# TouScruino-v0.net
KiCad netlist of a schematic drawn in EAGLE
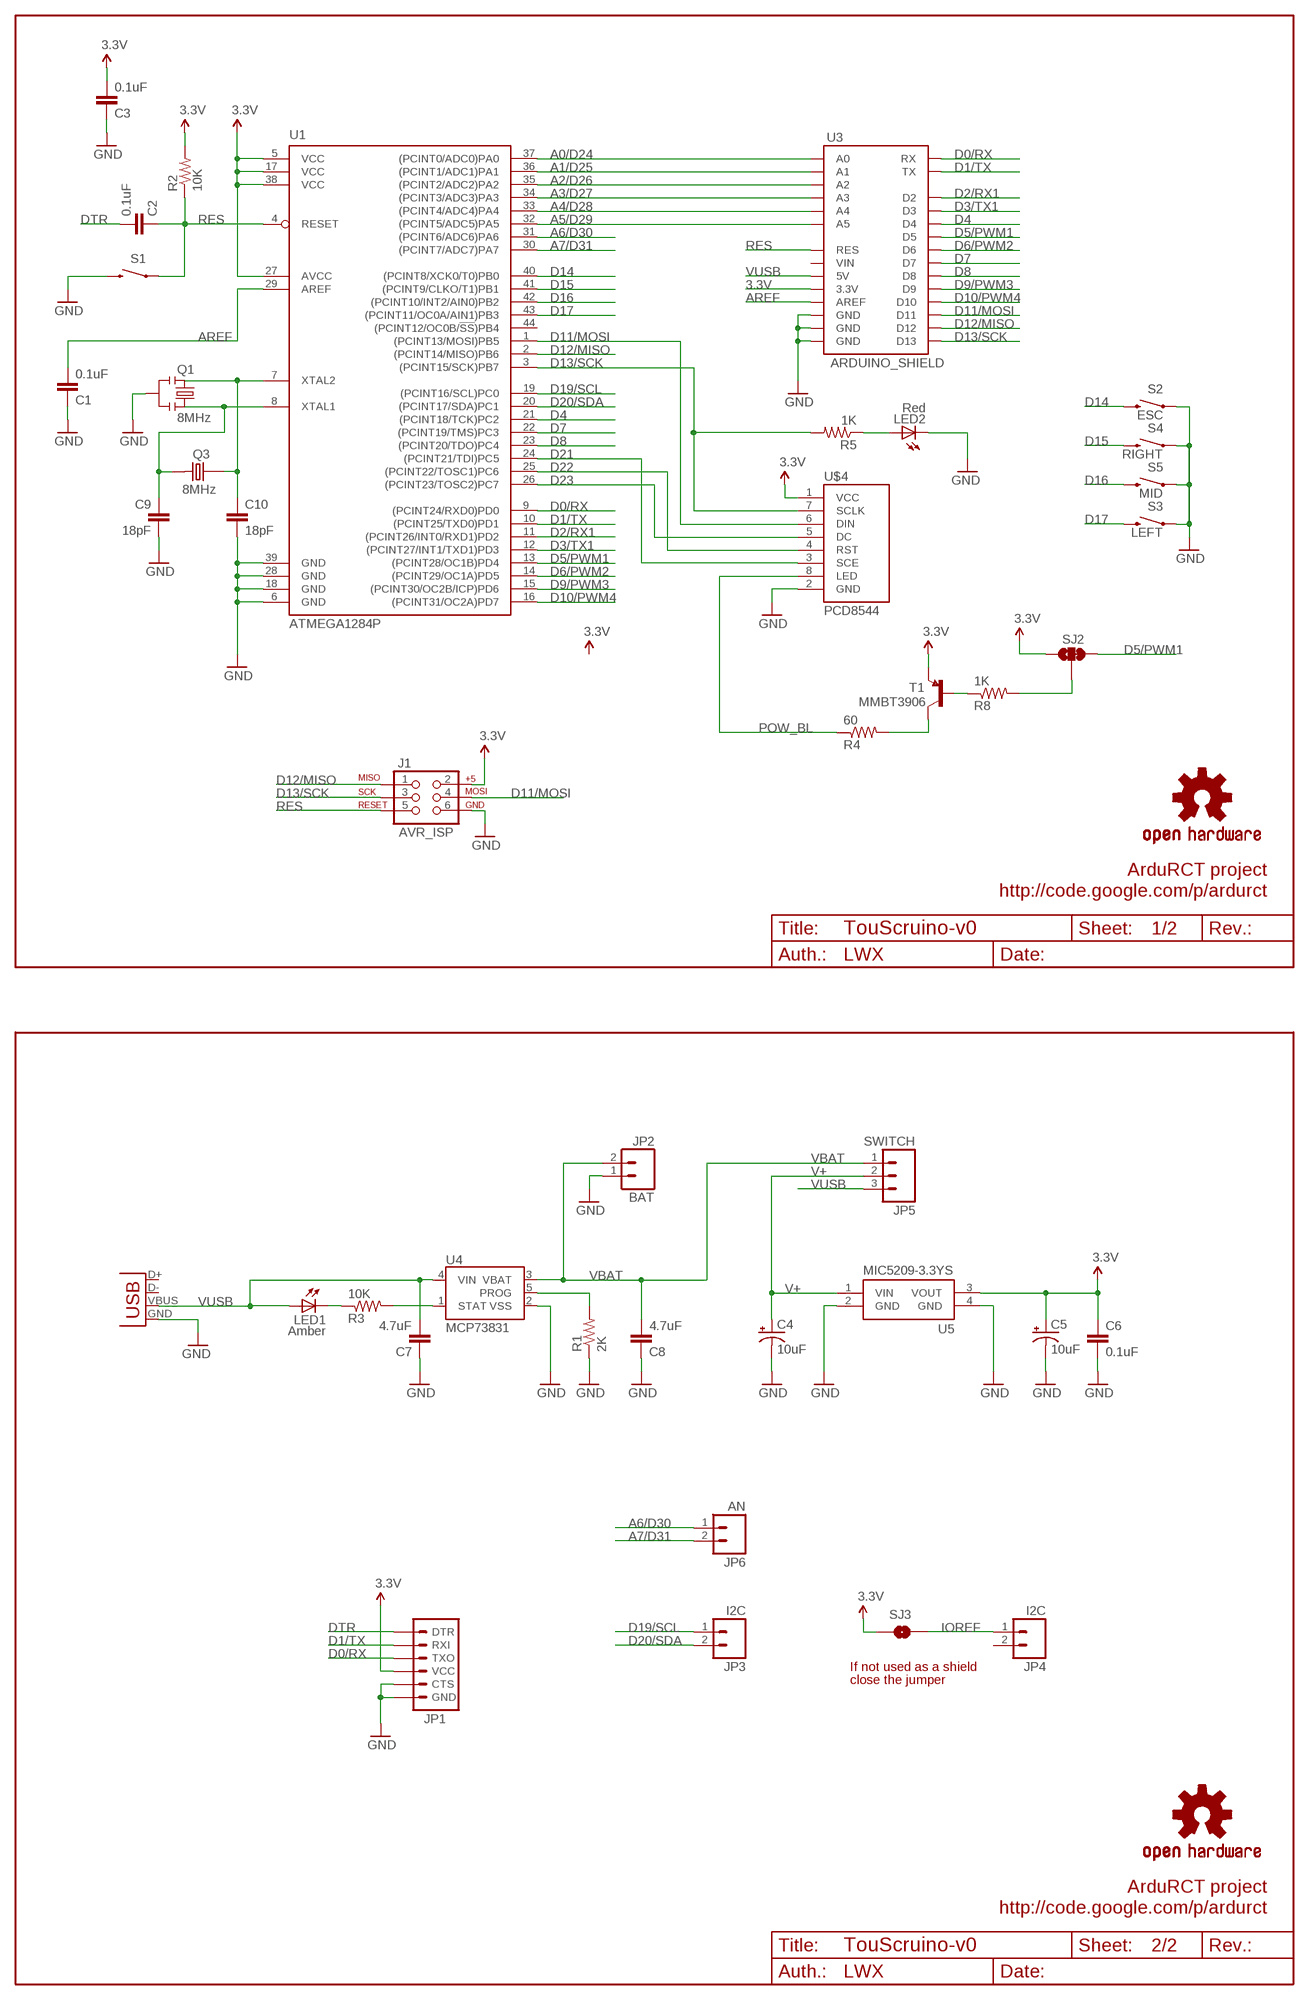
[diagram p0: schematic, sheet 1]

(export (version "E")
  (design (tool "Eeschema 10.0.6"))
  (components
    (comp (ref "C1")
      (value "0.1uF")
      (footprint "eagle-import:0805")
      (libsource (lib "eagle-import") (part "CAP0805"))
    )
    (comp (ref "C2")
      (value "0.1uF")
      (footprint "eagle-import:0805")
      (libsource (lib "eagle-import") (part "CAP0805"))
    )
    (comp (ref "C3")
      (value "0.1uF")
      (footprint "eagle-import:0805")
      (libsource (lib "eagle-import") (part "CAP0805"))
    )
    (comp (ref "C4")
      (value "10uF")
      (footprint "eagle-import:EIA3216")
      (libsource (lib "eagle-import") (part "CAP_POL1206"))
    )
    (comp (ref "C5")
      (value "10uF")
      (footprint "eagle-import:EIA3216")
      (libsource (lib "eagle-import") (part "CAP_POL1206"))
    )
    (comp (ref "C6")
      (value "0.1uF")
      (footprint "eagle-import:0805")
      (libsource (lib "eagle-import") (part "CAP0805"))
    )
    (comp (ref "C7")
      (value "4.7uF")
      (footprint "eagle-import:0805")
      (libsource (lib "eagle-import") (part "CAP0805"))
    )
    (comp (ref "C8")
      (value "4.7uF")
      (footprint "eagle-import:0805")
      (libsource (lib "eagle-import") (part "CAP0805"))
    )
    (comp (ref "C9")
      (value "18pF")
      (footprint "eagle-import:0603-CAP")
      (libsource (lib "eagle-import") (part "CAP0603-CAP"))
    )
    (comp (ref "C10")
      (value "18pF")
      (footprint "eagle-import:0603-CAP")
      (libsource (lib "eagle-import") (part "CAP0603-CAP"))
    )
    (comp (ref "J1")
      (value "AVR_ISP")
      (footprint "eagle-import:2X3")
      (libsource (lib "eagle-import") (part "AVR_SPI_PRG_6PTH"))
    )
    (comp (ref "JP1")
      (value "ARDUINO_SERIAL_PROGRAMPTH")
      (footprint "eagle-import:1X06")
      (libsource (lib "eagle-import") (part "ARDUINO_SERIAL_PROGRAMPTH"))
    )
    (comp (ref "JP2")
      (value "BAT")
      (footprint "eagle-import:JST-2-SMD")
      (libsource (lib "eagle-import") (part "M02-JST-2MM-SMT"))
    )
    (comp (ref "JP3")
      (value "I2C")
      (footprint "eagle-import:1X02")
      (libsource (lib "eagle-import") (part "M02"))
    )
    (comp (ref "JP4")
      (value "I2C")
      (footprint "eagle-import:1X02")
      (libsource (lib "eagle-import") (part "M02"))
    )
    (comp (ref "JP5")
      (value "SWITCH")
      (footprint "eagle-import:1X3_LONGPAD")
      (libsource (lib "eagle-import") (part "M03"))
    )
    (comp (ref "JP6")
      (value "AN")
      (footprint "eagle-import:1X02")
      (libsource (lib "eagle-import") (part "M02"))
    )
    (comp (ref "LED1")
      (value "Amber")
      (footprint "eagle-import:LED")
      (libsource (lib "eagle-import") (part "LED"))
    )
    (comp (ref "LED2")
      (value "Red")
      (footprint "eagle-import:LED-0805")
      (libsource (lib "eagle-import") (part "LED805"))
    )
    (comp (ref "Q1")
      (value "8MHz")
      (footprint "eagle-import:RESONATOR-SMD")
      (libsource (lib "eagle-import") (part "RESONATORSMD"))
    )
    (comp (ref "Q3")
      (value "8MHz")
      (footprint "eagle-import:CRYSTAL_5X3.2")
      (libsource (lib "eagle-import") (part "CRYSTAL_5X3.2"))
    )
    (comp (ref "R1")
      (value "2K")
      (footprint "eagle-import:0805")
      (libsource (lib "eagle-import") (part "RESISTOR0805-RES"))
    )
    (comp (ref "R2")
      (value "10K")
      (footprint "eagle-import:0805")
      (libsource (lib "eagle-import") (part "RESISTOR0805-RES"))
    )
    (comp (ref "R3")
      (value "10K")
      (footprint "eagle-import:0805")
      (libsource (lib "eagle-import") (part "RESISTOR0805-RES"))
    )
    (comp (ref "R4")
      (value "60")
      (footprint "eagle-import:0805")
      (libsource (lib "eagle-import") (part "RESISTOR0805-RES"))
    )
    (comp (ref "R5")
      (value "1K")
      (footprint "eagle-import:0805")
      (libsource (lib "eagle-import") (part "RESISTOR0805-RES"))
    )
    (comp (ref "R8")
      (value "1K")
      (footprint "eagle-import:0805")
      (libsource (lib "eagle-import") (part "RESISTOR0805-RES"))
    )
    (comp (ref "S1")
      (value "SWITCH-MOMENTARY-2SMD")
      (footprint "eagle-import:TACTILE_SWITCH_SMD@1")
      (libsource (lib "eagle-import") (part "SWITCH-MOMENTARY-2SMD"))
    )
    (comp (ref "S2")
      (value "ESC")
      (footprint "eagle-import:TACTILE_SWITCH_SMD")
      (libsource (lib "eagle-import") (part "SWITCH_SMD"))
    )
    (comp (ref "S3")
      (value "LEFT")
      (footprint "eagle-import:TACTILE_SWITCH_SMD")
      (libsource (lib "eagle-import") (part "SWITCH_SMD"))
    )
    (comp (ref "S4")
      (value "RIGHT")
      (footprint "eagle-import:TACTILE_SWITCH_SMD")
      (libsource (lib "eagle-import") (part "SWITCH_SMD"))
    )
    (comp (ref "S5")
      (value "MID")
      (footprint "eagle-import:TACTILE_SWITCH_SMD")
      (libsource (lib "eagle-import") (part "SWITCH_SMD"))
    )
    (comp (ref "SJ2")
      (value "SJ_2WAYS_1-2")
      (footprint "eagle-import:SJ_2WAYS_1-2_S")
      (libsource (lib "eagle-import") (part "SJ_2WAYS_1-2"))
    )
    (comp (ref "SJ3")
      (value "SOLDERJUMPERNO")
      (footprint "eagle-import:SJ_2S-NO")
      (libsource (lib "eagle-import") (part "SOLDERJUMPERNO"))
    )
    (comp (ref "T1")
      (value "MMBT3906")
      (footprint "eagle-import:SOT23-3")
      (libsource (lib "eagle-import") (part "TRANSISTOR_PNPSMD"))
    )
    (comp (ref "U$3")
      (value "OSHW-LOGOM")
      (footprint "eagle-import:OSHW-LOGO-M")
      (libsource (lib "eagle-import") (part "OSHW-LOGOM"))
    )
    (comp (ref "U$4")
      (value "PCD8544")
      (footprint "eagle-import:PCD8544")
      (libsource (lib "eagle-import") (part "PCD8544"))
    )
    (comp (ref "U$5")
      (value "OSHW-LOGOM")
      (footprint "eagle-import:OSHW-LOGO-M")
      (libsource (lib "eagle-import") (part "OSHW-LOGOM"))
    )
    (comp (ref "U1")
      (value "ATMEGA1284P")
      (footprint "eagle-import:TQFP44")
      (libsource (lib "eagle-import") (part "ATMEGA324A"))
    )
    (comp (ref "U3")
      (value "ARDUINO_SHIELD")
      (footprint "eagle-import:ARDUINO_SHIELD")
      (libsource (lib "eagle-import") (part "ARDUINO_SHIELD"))
    )
    (comp (ref "U4")
      (value "MCP73831")
      (footprint "eagle-import:SOT23-5")
      (libsource (lib "eagle-import") (part "MCP73831"))
    )
    (comp (ref "U5")
      (value "MIC5209-3.3YS")
      (footprint "eagle-import:SOT223")
      (libsource (lib "eagle-import") (part "MIC5209"))
    )
    (comp (ref "X1")
      (value "USBSMD")
      (footprint "eagle-import:USB-MINIB")
      (libsource (lib "eagle-import") (part "USBSMD"))
    )
  )
  (nets
    (net (code "1") (name "/A0{slash}D24") (class "Default")
      (node (ref "U1") (pin "37") (pinfunction "(PCINT0/ADC0)PA0_37") (pintype "bidirectional"))
      (node (ref "U3") (pin "A0") (pinfunction "A0_A0") (pintype "bidirectional"))
    )
    (net (code "2") (name "/A1{slash}D25") (class "Default")
      (node (ref "U1") (pin "36") (pinfunction "(PCINT1/ADC1)PA1_36") (pintype "bidirectional"))
      (node (ref "U3") (pin "A1") (pinfunction "A1_A1") (pintype "bidirectional"))
    )
    (net (code "3") (name "/A2{slash}D26") (class "Default")
      (node (ref "U1") (pin "35") (pinfunction "(PCINT2/ADC2)PA2_35") (pintype "bidirectional"))
      (node (ref "U3") (pin "A2") (pinfunction "A2_A2") (pintype "bidirectional"))
    )
    (net (code "4") (name "/A3{slash}D27") (class "Default")
      (node (ref "U1") (pin "34") (pinfunction "(PCINT3/ADC3)PA3_34") (pintype "bidirectional"))
      (node (ref "U3") (pin "A3") (pinfunction "A3_A3") (pintype "bidirectional"))
    )
    (net (code "5") (name "/A4{slash}D28") (class "Default")
      (node (ref "U1") (pin "33") (pinfunction "(PCINT4/ADC4)PA4_33") (pintype "bidirectional"))
      (node (ref "U3") (pin "A4") (pinfunction "A4_A4") (pintype "bidirectional"))
    )
    (net (code "6") (name "/A5{slash}D29") (class "Default")
      (node (ref "U1") (pin "32") (pinfunction "(PCINT5/ADC5)PA5_32") (pintype "bidirectional"))
      (node (ref "U3") (pin "A5") (pinfunction "A5_A5") (pintype "bidirectional"))
    )
    (net (code "7") (name "/A6{slash}D30") (class "Default")
      (node (ref "JP6") (pin "1") (pinfunction "1_1") (pintype "passive"))
      (node (ref "U1") (pin "31") (pinfunction "(PCINT6/ADC6)PA6_31") (pintype "bidirectional"))
    )
    (net (code "8") (name "/A7{slash}D31") (class "Default")
      (node (ref "JP6") (pin "2") (pinfunction "2_2") (pintype "passive"))
      (node (ref "U1") (pin "30") (pinfunction "(PCINT7/ADC7)PA7_30") (pintype "bidirectional"))
    )
    (net (code "9") (name "/AREF") (class "Default")
      (node (ref "C1") (pin "2") (pinfunction "2_2") (pintype "passive"))
      (node (ref "U1") (pin "29") (pinfunction "AREF_29") (pintype "passive"))
      (node (ref "U3") (pin "AREF") (pinfunction "AREF_AREF") (pintype "bidirectional"))
    )
    (net (code "10") (name "/D0{slash}RX") (class "Default")
      (node (ref "JP1") (pin "3") (pinfunction "TXO_3") (pintype "passive"))
      (node (ref "U1") (pin "9") (pinfunction "(PCINT24/RXD0)PD0_9") (pintype "bidirectional"))
      (node (ref "U3") (pin "RX") (pinfunction "RX_RX") (pintype "bidirectional"))
    )
    (net (code "11") (name "/D1{slash}TX") (class "Default")
      (node (ref "JP1") (pin "2") (pinfunction "RXI_2") (pintype "passive"))
      (node (ref "U1") (pin "10") (pinfunction "(PCINT25/TXD0)PD1_10") (pintype "bidirectional"))
      (node (ref "U3") (pin "TX") (pinfunction "TX_TX") (pintype "bidirectional"))
    )
    (net (code "12") (name "/D2{slash}RX1") (class "Default")
      (node (ref "U1") (pin "11") (pinfunction "(PCINT26/INT0/RXD1)PD2_11") (pintype "bidirectional"))
      (node (ref "U3") (pin "D2") (pinfunction "D2_D2") (pintype "bidirectional"))
    )
    (net (code "13") (name "/D3{slash}TX1") (class "Default")
      (node (ref "U1") (pin "12") (pinfunction "(PCINT27/INT1/TXD1)PD3_12") (pintype "bidirectional"))
      (node (ref "U3") (pin "D3") (pinfunction "D3_D3") (pintype "bidirectional"))
    )
    (net (code "14") (name "/D4") (class "Default")
      (node (ref "U1") (pin "21") (pinfunction "(PCINT18/TCK)PC2_21") (pintype "output"))
      (node (ref "U3") (pin "D4") (pinfunction "D4_D4") (pintype "bidirectional"))
    )
    (net (code "15") (name "/D5{slash}PWM1") (class "Default")
      (node (ref "SJ2") (pin "1") (pinfunction "1_1") (pintype "passive"))
      (node (ref "U1") (pin "13") (pinfunction "(PCINT28/OC1B)PD4_13") (pintype "bidirectional"))
      (node (ref "U3") (pin "D5") (pinfunction "D5_D5") (pintype "bidirectional"))
    )
    (net (code "16") (name "/D6{slash}PWM2") (class "Default")
      (node (ref "U1") (pin "14") (pinfunction "(PCINT29/OC1A)PD5_14") (pintype "bidirectional"))
      (node (ref "U3") (pin "D6") (pinfunction "D6_D6") (pintype "bidirectional"))
    )
    (net (code "17") (name "/D7") (class "Default")
      (node (ref "U1") (pin "22") (pinfunction "(PCINT19/TMS)PC3_22") (pintype "output"))
      (node (ref "U3") (pin "D7") (pinfunction "D7_D7") (pintype "bidirectional"))
    )
    (net (code "18") (name "/D8") (class "Default")
      (node (ref "U1") (pin "23") (pinfunction "(PCINT20/TDO)PC4_23") (pintype "output"))
      (node (ref "U3") (pin "D8") (pinfunction "D8_D8") (pintype "bidirectional"))
    )
    (net (code "19") (name "/D9{slash}PWM3") (class "Default")
      (node (ref "U1") (pin "15") (pinfunction "(PCINT30/OC2B/ICP)PD6_15") (pintype "bidirectional"))
      (node (ref "U3") (pin "D9") (pinfunction "D9_D9") (pintype "bidirectional"))
    )
    (net (code "20") (name "/D10{slash}PWM4") (class "Default")
      (node (ref "U1") (pin "16") (pinfunction "(PCINT31/OC2A)PD7_16") (pintype "bidirectional"))
      (node (ref "U3") (pin "D10") (pinfunction "D10_D10") (pintype "bidirectional"))
    )
    (net (code "21") (name "/D11{slash}MOSI") (class "Default")
      (node (ref "J1") (pin "4") (pinfunction "4_4") (pintype "passive"))
      (node (ref "U$4") (pin "6") (pinfunction "DIN_6") (pintype "bidirectional"))
      (node (ref "U1") (pin "1") (pinfunction "(PCINT13/MOSI)PB5_1") (pintype "bidirectional"))
      (node (ref "U3") (pin "D11") (pinfunction "D11_D11") (pintype "bidirectional"))
    )
    (net (code "22") (name "/D12{slash}MISO") (class "Default")
      (node (ref "J1") (pin "1") (pinfunction "1_1") (pintype "passive"))
      (node (ref "U1") (pin "2") (pinfunction "(PCINT14/MISO)PB6_2") (pintype "bidirectional"))
      (node (ref "U3") (pin "D12") (pinfunction "D12_D12") (pintype "bidirectional"))
    )
    (net (code "23") (name "/D13{slash}SCK") (class "Default")
      (node (ref "J1") (pin "3") (pinfunction "3_3") (pintype "passive"))
      (node (ref "R5") (pin "2") (pinfunction "2_2") (pintype "passive"))
      (node (ref "U$4") (pin "7") (pinfunction "SCLK_7") (pintype "bidirectional"))
      (node (ref "U1") (pin "3") (pinfunction "(PCINT15/SCK)PB7_3") (pintype "bidirectional"))
      (node (ref "U3") (pin "D13") (pinfunction "D13_D13") (pintype "bidirectional"))
    )
    (net (code "24") (name "/D14") (class "Default")
      (node (ref "S2") (pin "3") (pinfunction "2_3") (pintype "passive"))
      (node (ref "U1") (pin "40") (pinfunction "(PCINT8/XCK0/T0)PB0_40") (pintype "bidirectional"))
    )
    (net (code "25") (name "/D15") (class "Default")
      (node (ref "S4") (pin "3") (pinfunction "2_3") (pintype "passive"))
      (node (ref "U1") (pin "41") (pinfunction "(PCINT9/CLKO/T1)PB1_41") (pintype "bidirectional"))
    )
    (net (code "26") (name "/D16") (class "Default")
      (node (ref "S5") (pin "3") (pinfunction "2_3") (pintype "passive"))
      (node (ref "U1") (pin "42") (pinfunction "(PCINT10/INT2/AIN0)PB2_42") (pintype "bidirectional"))
    )
    (net (code "27") (name "/D17") (class "Default")
      (node (ref "S3") (pin "3") (pinfunction "2_3") (pintype "passive"))
      (node (ref "U1") (pin "43") (pinfunction "(PCINT11/OC0A/AIN1)PB3_43") (pintype "bidirectional"))
    )
    (net (code "28") (name "/D19{slash}SCL") (class "Default")
      (node (ref "JP3") (pin "1") (pinfunction "1_1") (pintype "passive"))
      (node (ref "U1") (pin "19") (pinfunction "(PCINT16/SCL)PC0_19") (pintype "output"))
    )
    (net (code "29") (name "/D20{slash}SDA") (class "Default")
      (node (ref "JP3") (pin "2") (pinfunction "2_2") (pintype "passive"))
      (node (ref "U1") (pin "20") (pinfunction "(PCINT17/SDA)PC1_20") (pintype "output"))
    )
    (net (code "30") (name "/D21") (class "Default")
      (node (ref "U$4") (pin "3") (pinfunction "SCE_3") (pintype "bidirectional"))
      (node (ref "U1") (pin "24") (pinfunction "(PCINT21/TDI)PC5_24") (pintype "output"))
    )
    (net (code "31") (name "/D22") (class "Default")
      (node (ref "U$4") (pin "4") (pinfunction "RST_4") (pintype "bidirectional"))
      (node (ref "U1") (pin "25") (pinfunction "(PCINT22/TOSC1)PC6_25") (pintype "output"))
    )
    (net (code "32") (name "/D23") (class "Default")
      (node (ref "U$4") (pin "5") (pinfunction "DC_5") (pintype "bidirectional"))
      (node (ref "U1") (pin "26") (pinfunction "(PCINT23/TOSC2)PC7_26") (pintype "output"))
    )
    (net (code "33") (name "/DTR") (class "Default")
      (node (ref "C2") (pin "2") (pinfunction "2_2") (pintype "passive"))
      (node (ref "JP1") (pin "1") (pinfunction "DTR_1") (pintype "passive"))
    )
    (net (code "34") (name "/IOREF") (class "Default")
      (node (ref "JP4") (pin "1") (pinfunction "1_1") (pintype "passive"))
      (node (ref "SJ3") (pin "2") (pinfunction "2_2") (pintype "passive"))
    )
    (net (code "35") (name "/POW_BL") (class "Default")
      (node (ref "R4") (pin "1") (pinfunction "1_1") (pintype "passive"))
      (node (ref "U$4") (pin "8") (pinfunction "LED_8") (pintype "bidirectional"))
    )
    (net (code "36") (name "/RES") (class "Default")
      (node (ref "C2") (pin "1") (pinfunction "1_1") (pintype "passive"))
      (node (ref "J1") (pin "5") (pinfunction "5_5") (pintype "passive"))
      (node (ref "R2") (pin "1") (pinfunction "1_1") (pintype "passive"))
      (node (ref "S1") (pin "1") (pinfunction "1_1") (pintype "passive"))
      (node (ref "U1") (pin "4") (pinfunction "RESET_4") (pintype "input"))
      (node (ref "U3") (pin "RES") (pinfunction "RES_RES") (pintype "bidirectional"))
    )
    (net (code "37") (name "/V+") (class "Default")
      (node (ref "C4") (pin "A") (pinfunction "+_A") (pintype "passive"))
      (node (ref "JP5") (pin "2") (pinfunction "2_2") (pintype "passive"))
      (node (ref "U5") (pin "1") (pinfunction "VIN_1") (pintype "bidirectional"))
    )
    (net (code "38") (name "/VBAT") (class "Default")
      (node (ref "C8") (pin "2") (pinfunction "2_2") (pintype "passive"))
      (node (ref "JP2") (pin "2") (pinfunction "2_2") (pintype "passive"))
      (node (ref "JP5") (pin "1") (pinfunction "1_1") (pintype "passive"))
      (node (ref "U4") (pin "3") (pinfunction "VBAT_3") (pintype "power_in"))
    )
    (net (code "39") (name "/VUSB") (class "Default")
      (node (ref "C7") (pin "2") (pinfunction "2_2") (pintype "passive"))
      (node (ref "JP5") (pin "3") (pinfunction "3_3") (pintype "passive"))
      (node (ref "LED1") (pin "A1") (pinfunction "A_A1") (pintype "passive"))
      (node (ref "U3") (pin "5V") (pinfunction "5V_5V") (pintype "bidirectional"))
      (node (ref "U4") (pin "4") (pinfunction "VIN_4") (pintype "power_in"))
      (node (ref "X1") (pin "VBUS") (pinfunction "VBUS_VBUS") (pintype "bidirectional"))
    )
    (net (code "40") (name "3.3V") (class "Default")
      (node (ref "C3") (pin "2") (pinfunction "2_2") (pintype "passive"))
      (node (ref "C5") (pin "A") (pinfunction "+_A") (pintype "passive"))
      (node (ref "C6") (pin "1") (pinfunction "1_1") (pintype "passive"))
      (node (ref "J1") (pin "2") (pinfunction "2_2") (pintype "passive"))
      (node (ref "JP1") (pin "4") (pinfunction "VCC_4") (pintype "passive"))
      (node (ref "R2") (pin "2") (pinfunction "2_2") (pintype "passive"))
      (node (ref "SJ2") (pin "3") (pinfunction "3_3") (pintype "passive"))
      (node (ref "SJ3") (pin "1") (pinfunction "1_1") (pintype "passive"))
      (node (ref "T1") (pin "2") (pinfunction "E_2") (pintype "passive"))
      (node (ref "U$4") (pin "1") (pinfunction "VCC_1") (pintype "bidirectional"))
      (node (ref "U1") (pin "17") (pinfunction "VCC_17") (pintype "power_in"))
      (node (ref "U1") (pin "27") (pinfunction "AVCC_27") (pintype "power_in"))
      (node (ref "U1") (pin "38") (pinfunction "VCC_38") (pintype "power_in"))
      (node (ref "U1") (pin "5") (pinfunction "VCC_5") (pintype "power_in"))
      (node (ref "U3") (pin "3.3V") (pinfunction "3.3V_3.3V") (pintype "bidirectional"))
      (node (ref "U5") (pin "3") (pinfunction "VOUT_3") (pintype "bidirectional"))
    )
    (net (code "41") (name "GND") (class "Default")
      (node (ref "C1") (pin "1") (pinfunction "1_1") (pintype "passive"))
      (node (ref "C10") (pin "2") (pinfunction "2_2") (pintype "passive"))
      (node (ref "C3") (pin "1") (pinfunction "1_1") (pintype "passive"))
      (node (ref "C4") (pin "C") (pinfunction "-_C") (pintype "passive"))
      (node (ref "C5") (pin "C") (pinfunction "-_C") (pintype "passive"))
      (node (ref "C6") (pin "2") (pinfunction "2_2") (pintype "passive"))
      (node (ref "C7") (pin "1") (pinfunction "1_1") (pintype "passive"))
      (node (ref "C8") (pin "1") (pinfunction "1_1") (pintype "passive"))
      (node (ref "C9") (pin "2") (pinfunction "2_2") (pintype "passive"))
      (node (ref "J1") (pin "6") (pinfunction "6_6") (pintype "passive"))
      (node (ref "JP1") (pin "5") (pinfunction "CTS_5") (pintype "passive"))
      (node (ref "JP1") (pin "6") (pinfunction "GND_6") (pintype "passive"))
      (node (ref "JP2") (pin "1") (pinfunction "1_1") (pintype "passive"))
      (node (ref "LED2") (pin "2") (pinfunction "C_2") (pintype "passive"))
      (node (ref "Q1") (pin "2") (pinfunction "2_2") (pintype "passive"))
      (node (ref "R1") (pin "1") (pinfunction "1_1") (pintype "passive"))
      (node (ref "S1") (pin "3") (pinfunction "2_3") (pintype "passive"))
      (node (ref "S2") (pin "1") (pinfunction "1_1") (pintype "passive"))
      (node (ref "S3") (pin "1") (pinfunction "1_1") (pintype "passive"))
      (node (ref "S4") (pin "1") (pinfunction "1_1") (pintype "passive"))
      (node (ref "S5") (pin "1") (pinfunction "1_1") (pintype "passive"))
      (node (ref "U$4") (pin "2") (pinfunction "GND_2") (pintype "bidirectional"))
      (node (ref "U1") (pin "18") (pinfunction "GND_18") (pintype "power_in"))
      (node (ref "U1") (pin "28") (pinfunction "GND_28") (pintype "power_in"))
      (node (ref "U1") (pin "39") (pinfunction "GND_39") (pintype "power_in"))
      (node (ref "U1") (pin "6") (pinfunction "GND_6") (pintype "power_in"))
      (node (ref "U3") (pin "GND@0") (pinfunction "GND_GND@0") (pintype "bidirectional"))
      (node (ref "U3") (pin "GND@1") (pinfunction "GND_GND@1") (pintype "bidirectional"))
      (node (ref "U3") (pin "GND@2") (pinfunction "GND_GND@2") (pintype "bidirectional"))
      (node (ref "U4") (pin "2") (pinfunction "VSS_2") (pintype "power_in"))
      (node (ref "U5") (pin "2") (pinfunction "GND_2") (pintype "bidirectional"))
      (node (ref "U5") (pin "4") (pinfunction "GND_4") (pintype "bidirectional"))
      (node (ref "X1") (pin "GND") (pinfunction "GND_GND") (pintype "bidirectional"))
    )
    (net (code "42") (name "Net-(LED1-C)") (class "Default")
      (node (ref "LED1") (pin "C1") (pinfunction "C_C1") (pintype "passive"))
      (node (ref "R3") (pin "1") (pinfunction "1_1") (pintype "passive"))
    )
    (net (code "43") (name "Net-(LED2-A)") (class "Default")
      (node (ref "LED2") (pin "1") (pinfunction "A_1") (pintype "passive"))
      (node (ref "R5") (pin "1") (pinfunction "1_1") (pintype "passive"))
    )
    (net (code "44") (name "Net-(R8-Pad2)") (class "Default")
      (node (ref "R8") (pin "2") (pinfunction "2_2") (pintype "passive"))
      (node (ref "SJ2") (pin "2") (pinfunction "2_2") (pintype "passive"))
    )
    (net (code "45") (name "Net-(T1-B)") (class "Default")
      (node (ref "R8") (pin "1") (pinfunction "1_1") (pintype "passive"))
      (node (ref "T1") (pin "1") (pinfunction "B_1") (pintype "passive"))
    )
    (net (code "46") (name "Net-(T1-C)") (class "Default")
      (node (ref "R4") (pin "2") (pinfunction "2_2") (pintype "passive"))
      (node (ref "T1") (pin "3") (pinfunction "C_3") (pintype "passive"))
    )
    (net (code "47") (name "Net-(U1-XTAL1)") (class "Default")
      (node (ref "C9") (pin "1") (pinfunction "1_1") (pintype "passive"))
      (node (ref "Q1") (pin "1") (pinfunction "1_1") (pintype "passive"))
      (node (ref "Q3") (pin "2") (pinfunction "2_2") (pintype "passive"))
      (node (ref "U1") (pin "8") (pinfunction "XTAL1_8") (pintype "bidirectional"))
    )
    (net (code "48") (name "Net-(U1-XTAL2)") (class "Default")
      (node (ref "C10") (pin "1") (pinfunction "1_1") (pintype "passive"))
      (node (ref "Q1") (pin "3") (pinfunction "3_3") (pintype "passive"))
      (node (ref "Q3") (pin "1") (pinfunction "1_1") (pintype "passive"))
      (node (ref "U1") (pin "7") (pinfunction "XTAL2_7") (pintype "bidirectional"))
    )
    (net (code "49") (name "Net-(U4-PROG)") (class "Default")
      (node (ref "R1") (pin "2") (pinfunction "2_2") (pintype "passive"))
      (node (ref "U4") (pin "5") (pinfunction "PROG_5") (pintype "input"))
    )
    (net (code "50") (name "Net-(U4-STAT)") (class "Default")
      (node (ref "R3") (pin "2") (pinfunction "2_2") (pintype "passive"))
      (node (ref "U4") (pin "1") (pinfunction "STAT_1") (pintype "output"))
    )
    (net (code "51") (name "unconnected-(JP4-Pad2)") (class "Default")
      (node (ref "JP4") (pin "2") (pinfunction "2_2") (pintype "passive"))
    )
    (net (code "52") (name "unconnected-(U1-(PCINT12{slash}OC0B{slash}~{SS})PB4-Pad44)") (class "Default")
      (node (ref "U1") (pin "44") (pinfunction "(PCINT12/OC0B/~{SS})PB4_44") (pintype "bidirectional"))
    )
    (net (code "53") (name "unconnected-(U3-PadVIN)") (class "Default")
      (node (ref "U3") (pin "VIN") (pinfunction "VIN_VIN") (pintype "bidirectional"))
    )
    (net (code "54") (name "unconnected-(X1-PadD+)") (class "Default")
      (node (ref "X1") (pin "D+") (pinfunction "D+_D+") (pintype "bidirectional"))
    )
    (net (code "55") (name "unconnected-(X1-PadD-)") (class "Default")
      (node (ref "X1") (pin "D-") (pinfunction "D-_D-") (pintype "bidirectional"))
    )
  )
)
